# FanManager.net
KiCad netlist of a schematic drawn in EAGLE
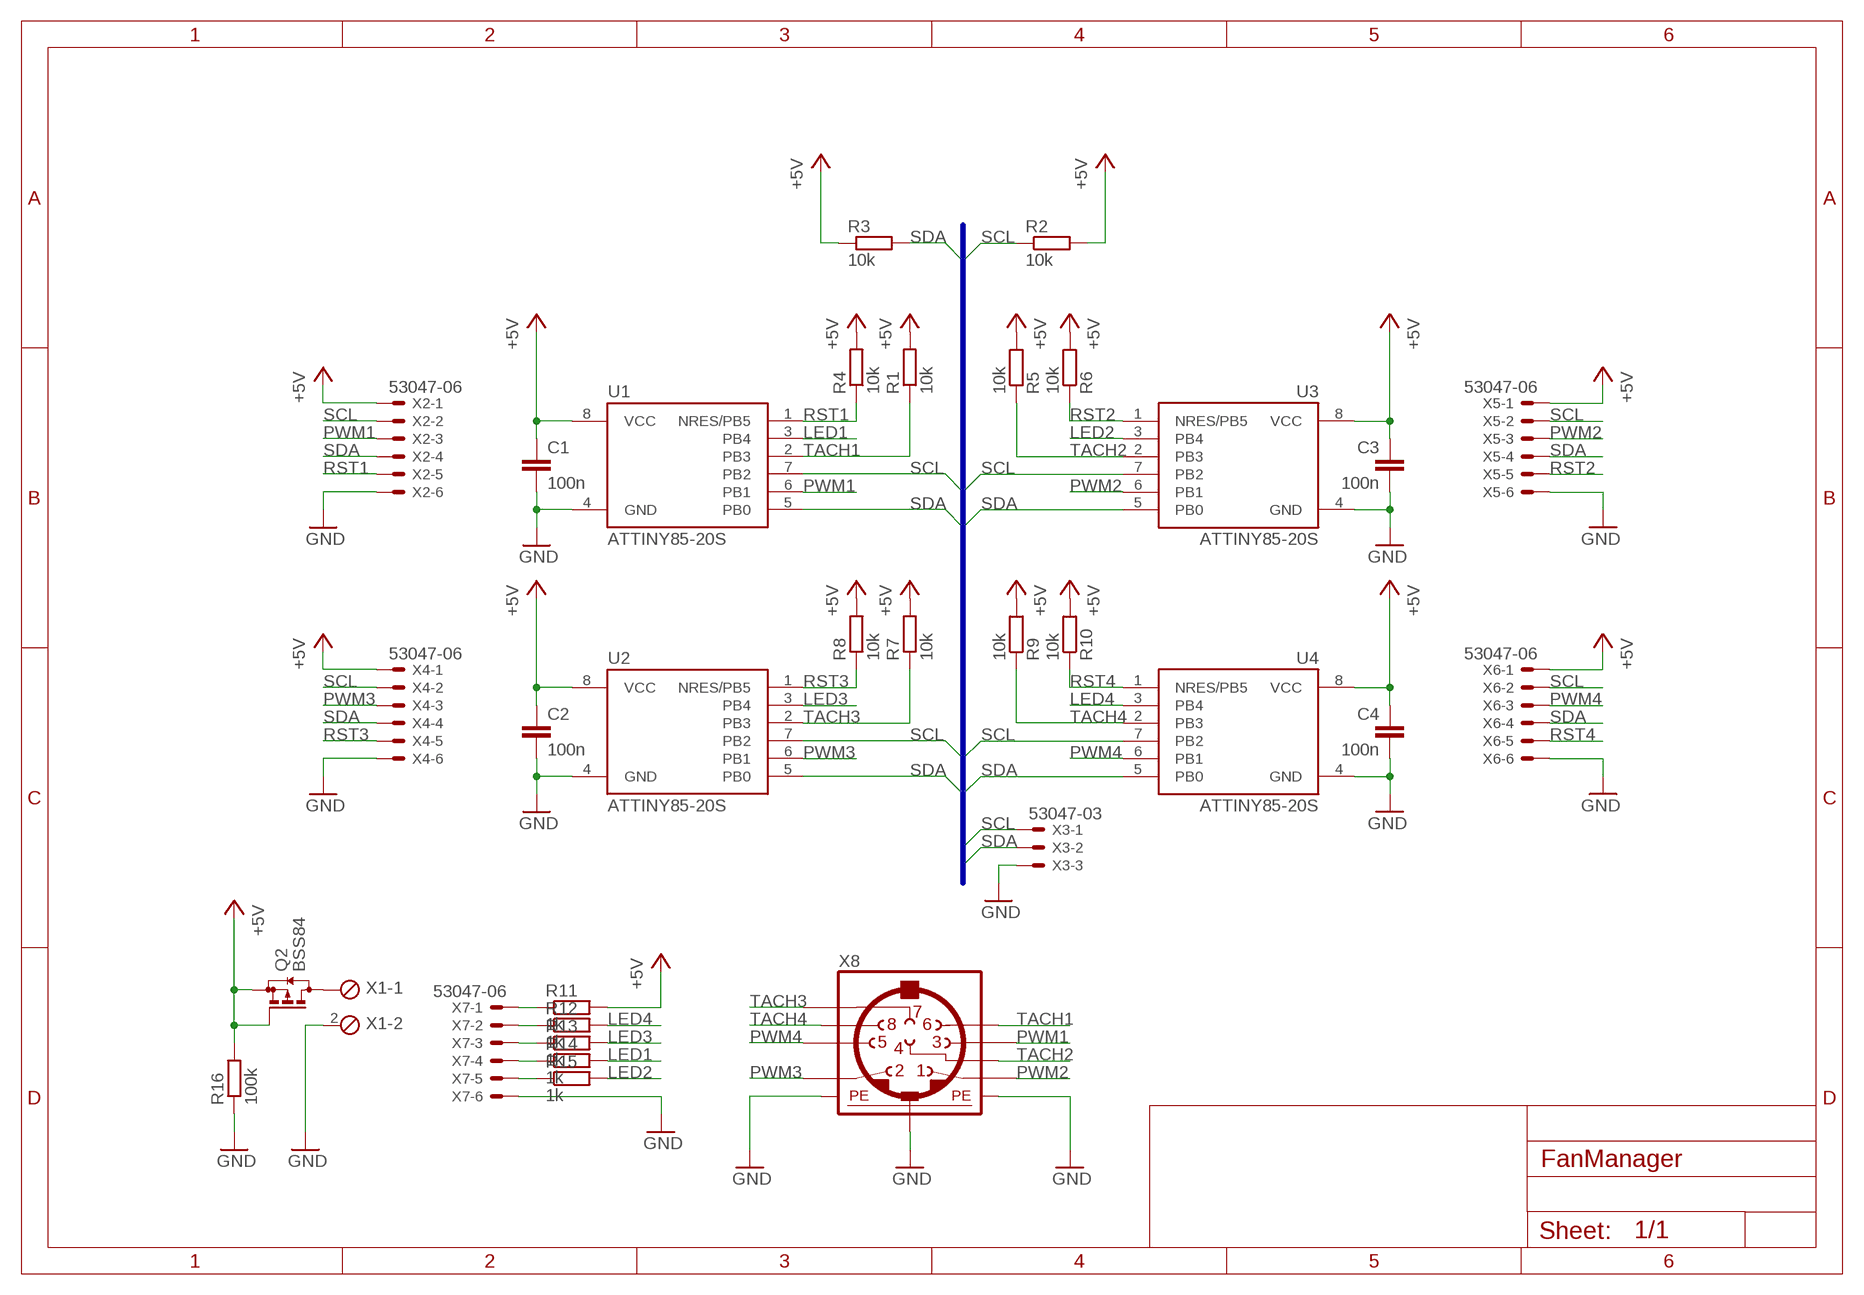
[diagram p0: schematic, sheet 1]

(export (version "E")
  (design (tool "Eeschema 10.0.6"))
  (components
    (comp (ref "C1")
      (value "100n")
      (footprint "eagle-import:C0805")
      (libsource (lib "eagle-import") (part "C-EUC0805"))
    )
    (comp (ref "C2")
      (value "100n")
      (footprint "eagle-import:C0805")
      (libsource (lib "eagle-import") (part "C-EUC0805"))
    )
    (comp (ref "C3")
      (value "100n")
      (footprint "eagle-import:C0805")
      (libsource (lib "eagle-import") (part "C-EUC0805"))
    )
    (comp (ref "C4")
      (value "100n")
      (footprint "eagle-import:C0805")
      (libsource (lib "eagle-import") (part "C-EUC0805"))
    )
    (comp (ref "Q2")
      (value "BSS84")
      (footprint "eagle-import:SOT23")
      (libsource (lib "eagle-import") (part "BSS84"))
    )
    (comp (ref "R1")
      (value "10k")
      (footprint "eagle-import:R0805")
      (libsource (lib "eagle-import") (part "R-EU_R0805"))
    )
    (comp (ref "R2")
      (value "10k")
      (footprint "eagle-import:R0805")
      (libsource (lib "eagle-import") (part "R-EU_R0805"))
    )
    (comp (ref "R3")
      (value "10k")
      (footprint "eagle-import:R0805")
      (libsource (lib "eagle-import") (part "R-EU_R0805"))
    )
    (comp (ref "R4")
      (value "10k")
      (footprint "eagle-import:R0805")
      (libsource (lib "eagle-import") (part "R-EU_R0805"))
    )
    (comp (ref "R5")
      (value "10k")
      (footprint "eagle-import:R0805")
      (libsource (lib "eagle-import") (part "R-EU_R0805"))
    )
    (comp (ref "R6")
      (value "10k")
      (footprint "eagle-import:R0805")
      (libsource (lib "eagle-import") (part "R-EU_R0805"))
    )
    (comp (ref "R7")
      (value "10k")
      (footprint "eagle-import:R0805")
      (libsource (lib "eagle-import") (part "R-EU_R0805"))
    )
    (comp (ref "R8")
      (value "10k")
      (footprint "eagle-import:R0805")
      (libsource (lib "eagle-import") (part "R-EU_R0805"))
    )
    (comp (ref "R9")
      (value "10k")
      (footprint "eagle-import:R0805")
      (libsource (lib "eagle-import") (part "R-EU_R0805"))
    )
    (comp (ref "R10")
      (value "10k")
      (footprint "eagle-import:R0805")
      (libsource (lib "eagle-import") (part "R-EU_R0805"))
    )
    (comp (ref "R11")
      (value "1k")
      (footprint "eagle-import:R0805")
      (libsource (lib "eagle-import") (part "R-EU_R0805"))
    )
    (comp (ref "R12")
      (value "1k")
      (footprint "eagle-import:R0805")
      (libsource (lib "eagle-import") (part "R-EU_R0805"))
    )
    (comp (ref "R13")
      (value "1k")
      (footprint "eagle-import:R0805")
      (libsource (lib "eagle-import") (part "R-EU_R0805"))
    )
    (comp (ref "R14")
      (value "1k")
      (footprint "eagle-import:R0805")
      (libsource (lib "eagle-import") (part "R-EU_R0805"))
    )
    (comp (ref "R15")
      (value "1k")
      (footprint "eagle-import:R0805")
      (libsource (lib "eagle-import") (part "R-EU_R0805"))
    )
    (comp (ref "R16")
      (value "100k")
      (footprint "eagle-import:R0805")
      (libsource (lib "eagle-import") (part "R-EU_R0805"))
    )
    (comp (ref "U1")
      (value "ATTINY85-20S")
      (footprint "eagle-import:SOIC8_EIAJ_208MIL")
      (libsource (lib "eagle-import") (part "ATTINY85S-20"))
    )
    (comp (ref "U2")
      (value "ATTINY85-20S")
      (footprint "eagle-import:SOIC8_EIAJ_208MIL")
      (libsource (lib "eagle-import") (part "ATTINY85S-20"))
    )
    (comp (ref "U3")
      (value "ATTINY85-20S")
      (footprint "eagle-import:SOIC8_EIAJ_208MIL")
      (libsource (lib "eagle-import") (part "ATTINY85S-20"))
    )
    (comp (ref "U4")
      (value "ATTINY85-20S")
      (footprint "eagle-import:SOIC8_EIAJ_208MIL")
      (libsource (lib "eagle-import") (part "ATTINY85S-20"))
    )
    (comp (ref "X1")
      (value "KLEMME_2XRAND_LANGPAD")
      (footprint "eagle-import:2POL254")
      (libsource (lib "eagle-import") (part "KLEMME_2XRAND_LANGPAD"))
    )
    (comp (ref "X2")
      (value "53047-06")
      (footprint "eagle-import:53047-06")
      (fields (field (name "MF") "MOLEX") (field (name "MPN") "53047-0610-C"))
      (libsource (lib "eagle-import") (part "53?-06047"))
    )
    (comp (ref "X3")
      (value "53047-03")
      (footprint "eagle-import:53047-03")
      (fields (field (name "MF") "MOLEX") (field (name "MPN") "530470310"))
      (libsource (lib "eagle-import") (part "53?-03047"))
    )
    (comp (ref "X4")
      (value "53047-06")
      (footprint "eagle-import:53047-06")
      (fields (field (name "MF") "MOLEX") (field (name "MPN") "53047-0610-C"))
      (libsource (lib "eagle-import") (part "53?-06047"))
    )
    (comp (ref "X5")
      (value "53047-06")
      (footprint "eagle-import:53047-06")
      (fields (field (name "MF") "MOLEX") (field (name "MPN") "53047-0610-C"))
      (libsource (lib "eagle-import") (part "53?-06047"))
    )
    (comp (ref "X6")
      (value "53047-06")
      (footprint "eagle-import:53047-06")
      (fields (field (name "MF") "MOLEX") (field (name "MPN") "53047-0610-C"))
      (libsource (lib "eagle-import") (part "53?-06047"))
    )
    (comp (ref "X7")
      (value "53047-06")
      (footprint "eagle-import:53047-06")
      (fields (field (name "MF") "MOLEX") (field (name "MPN") "53047-0610-C"))
      (libsource (lib "eagle-import") (part "53?-06047"))
    )
    (comp (ref "X8")
      (value "MINI_DIN_8")
      (footprint "eagle-import:M_DIN8")
      (libsource (lib "eagle-import") (part "MINI_DIN_8"))
    )
  )
  (nets
    (net (code "1") (name "+5V") (class "Default")
      (node (ref "C1") (pin "1") (pinfunction "1_1") (pintype "passive"))
      (node (ref "C2") (pin "1") (pinfunction "1_1") (pintype "passive"))
      (node (ref "C3") (pin "1") (pinfunction "1_1") (pintype "passive"))
      (node (ref "C4") (pin "1") (pinfunction "1_1") (pintype "passive"))
      (node (ref "Q2") (pin "1") (pinfunction "G_1") (pintype "passive"))
      (node (ref "Q2") (pin "2") (pinfunction "S_2") (pintype "passive"))
      (node (ref "R1") (pin "2") (pinfunction "2_2") (pintype "passive"))
      (node (ref "R10") (pin "2") (pinfunction "2_2") (pintype "passive"))
      (node (ref "R11") (pin "2") (pinfunction "2_2") (pintype "passive"))
      (node (ref "R16") (pin "2") (pinfunction "2_2") (pintype "passive"))
      (node (ref "R2") (pin "2") (pinfunction "2_2") (pintype "passive"))
      (node (ref "R3") (pin "1") (pinfunction "1_1") (pintype "passive"))
      (node (ref "R4") (pin "2") (pinfunction "2_2") (pintype "passive"))
      (node (ref "R5") (pin "2") (pinfunction "2_2") (pintype "passive"))
      (node (ref "R6") (pin "2") (pinfunction "2_2") (pintype "passive"))
      (node (ref "R7") (pin "2") (pinfunction "2_2") (pintype "passive"))
      (node (ref "R8") (pin "2") (pinfunction "2_2") (pintype "passive"))
      (node (ref "R9") (pin "2") (pinfunction "2_2") (pintype "passive"))
      (node (ref "U1") (pin "8") (pinfunction "VCC_8") (pintype "power_in"))
      (node (ref "U2") (pin "8") (pinfunction "VCC_8") (pintype "power_in"))
      (node (ref "U3") (pin "8") (pinfunction "VCC_8") (pintype "power_in"))
      (node (ref "U4") (pin "8") (pinfunction "VCC_8") (pintype "power_in"))
      (node (ref "X2") (pin "1") (pinfunction "S_1") (pintype "passive"))
      (node (ref "X4") (pin "1") (pinfunction "S_1") (pintype "passive"))
      (node (ref "X5") (pin "1") (pinfunction "S_1") (pintype "passive"))
      (node (ref "X6") (pin "1") (pinfunction "S_1") (pintype "passive"))
    )
    (net (code "2") (name "/LED1") (class "Default")
      (node (ref "R14") (pin "2") (pinfunction "2_2") (pintype "passive"))
      (node (ref "U1") (pin "3") (pinfunction "PB4_3") (pintype "bidirectional"))
    )
    (net (code "3") (name "/LED2") (class "Default")
      (node (ref "R15") (pin "2") (pinfunction "2_2") (pintype "passive"))
      (node (ref "U3") (pin "3") (pinfunction "PB4_3") (pintype "bidirectional"))
    )
    (net (code "4") (name "/LED3") (class "Default")
      (node (ref "R13") (pin "2") (pinfunction "2_2") (pintype "passive"))
      (node (ref "U2") (pin "3") (pinfunction "PB4_3") (pintype "bidirectional"))
    )
    (net (code "5") (name "/LED4") (class "Default")
      (node (ref "R12") (pin "2") (pinfunction "2_2") (pintype "passive"))
      (node (ref "U4") (pin "3") (pinfunction "PB4_3") (pintype "bidirectional"))
    )
    (net (code "6") (name "/PWM1") (class "Default")
      (node (ref "U1") (pin "6") (pinfunction "PB1_6") (pintype "bidirectional"))
      (node (ref "X2") (pin "3") (pinfunction "S_3") (pintype "passive"))
      (node (ref "X8") (pin "3") (pinfunction "3_3") (pintype "passive"))
    )
    (net (code "7") (name "/PWM2") (class "Default")
      (node (ref "U3") (pin "6") (pinfunction "PB1_6") (pintype "bidirectional"))
      (node (ref "X5") (pin "3") (pinfunction "S_3") (pintype "passive"))
      (node (ref "X8") (pin "1") (pinfunction "1_1") (pintype "passive"))
    )
    (net (code "8") (name "/PWM3") (class "Default")
      (node (ref "U2") (pin "6") (pinfunction "PB1_6") (pintype "bidirectional"))
      (node (ref "X4") (pin "3") (pinfunction "S_3") (pintype "passive"))
      (node (ref "X8") (pin "2") (pinfunction "2_2") (pintype "passive"))
    )
    (net (code "9") (name "/PWM4") (class "Default")
      (node (ref "U4") (pin "6") (pinfunction "PB1_6") (pintype "bidirectional"))
      (node (ref "X6") (pin "3") (pinfunction "S_3") (pintype "passive"))
      (node (ref "X8") (pin "5") (pinfunction "5_5") (pintype "passive"))
    )
    (net (code "10") (name "/RST1") (class "Default")
      (node (ref "R4") (pin "1") (pinfunction "1_1") (pintype "passive"))
      (node (ref "U1") (pin "1") (pinfunction "NRES/PB5_1") (pintype "bidirectional"))
      (node (ref "X2") (pin "5") (pinfunction "S_5") (pintype "passive"))
    )
    (net (code "11") (name "/RST2") (class "Default")
      (node (ref "R6") (pin "1") (pinfunction "1_1") (pintype "passive"))
      (node (ref "U3") (pin "1") (pinfunction "NRES/PB5_1") (pintype "bidirectional"))
      (node (ref "X5") (pin "5") (pinfunction "S_5") (pintype "passive"))
    )
    (net (code "12") (name "/RST3") (class "Default")
      (node (ref "R8") (pin "1") (pinfunction "1_1") (pintype "passive"))
      (node (ref "U2") (pin "1") (pinfunction "NRES/PB5_1") (pintype "bidirectional"))
      (node (ref "X4") (pin "5") (pinfunction "S_5") (pintype "passive"))
    )
    (net (code "13") (name "/RST4") (class "Default")
      (node (ref "R10") (pin "1") (pinfunction "1_1") (pintype "passive"))
      (node (ref "U4") (pin "1") (pinfunction "NRES/PB5_1") (pintype "bidirectional"))
      (node (ref "X6") (pin "5") (pinfunction "S_5") (pintype "passive"))
    )
    (net (code "14") (name "/SCL") (class "Default")
      (node (ref "R2") (pin "1") (pinfunction "1_1") (pintype "passive"))
      (node (ref "U1") (pin "7") (pinfunction "PB2_7") (pintype "bidirectional"))
      (node (ref "U2") (pin "7") (pinfunction "PB2_7") (pintype "bidirectional"))
      (node (ref "U3") (pin "7") (pinfunction "PB2_7") (pintype "bidirectional"))
      (node (ref "U4") (pin "7") (pinfunction "PB2_7") (pintype "bidirectional"))
      (node (ref "X2") (pin "2") (pinfunction "S_2") (pintype "passive"))
      (node (ref "X3") (pin "1") (pinfunction "S_1") (pintype "passive"))
      (node (ref "X4") (pin "2") (pinfunction "S_2") (pintype "passive"))
      (node (ref "X5") (pin "2") (pinfunction "S_2") (pintype "passive"))
      (node (ref "X6") (pin "2") (pinfunction "S_2") (pintype "passive"))
    )
    (net (code "15") (name "/SDA") (class "Default")
      (node (ref "R3") (pin "2") (pinfunction "2_2") (pintype "passive"))
      (node (ref "U1") (pin "5") (pinfunction "PB0_5") (pintype "bidirectional"))
      (node (ref "U2") (pin "5") (pinfunction "PB0_5") (pintype "bidirectional"))
      (node (ref "U3") (pin "5") (pinfunction "PB0_5") (pintype "bidirectional"))
      (node (ref "U4") (pin "5") (pinfunction "PB0_5") (pintype "bidirectional"))
      (node (ref "X2") (pin "4") (pinfunction "S_4") (pintype "passive"))
      (node (ref "X3") (pin "2") (pinfunction "S_2") (pintype "passive"))
      (node (ref "X4") (pin "4") (pinfunction "S_4") (pintype "passive"))
      (node (ref "X5") (pin "4") (pinfunction "S_4") (pintype "passive"))
      (node (ref "X6") (pin "4") (pinfunction "S_4") (pintype "passive"))
    )
    (net (code "16") (name "/TACH1") (class "Default")
      (node (ref "R1") (pin "1") (pinfunction "1_1") (pintype "passive"))
      (node (ref "U1") (pin "2") (pinfunction "PB3_2") (pintype "bidirectional"))
      (node (ref "X8") (pin "6") (pinfunction "6_6") (pintype "passive"))
    )
    (net (code "17") (name "/TACH2") (class "Default")
      (node (ref "R5") (pin "1") (pinfunction "1_1") (pintype "passive"))
      (node (ref "U3") (pin "2") (pinfunction "PB3_2") (pintype "bidirectional"))
      (node (ref "X8") (pin "4") (pinfunction "4_4") (pintype "passive"))
    )
    (net (code "18") (name "/TACH3") (class "Default")
      (node (ref "R7") (pin "1") (pinfunction "1_1") (pintype "passive"))
      (node (ref "U2") (pin "2") (pinfunction "PB3_2") (pintype "bidirectional"))
      (node (ref "X8") (pin "7") (pinfunction "7_7") (pintype "passive"))
    )
    (net (code "19") (name "/TACH4") (class "Default")
      (node (ref "R9") (pin "1") (pinfunction "1_1") (pintype "passive"))
      (node (ref "U4") (pin "2") (pinfunction "PB3_2") (pintype "bidirectional"))
      (node (ref "X8") (pin "8") (pinfunction "8_8") (pintype "passive"))
    )
    (net (code "20") (name "GND") (class "Default")
      (node (ref "C1") (pin "2") (pinfunction "2_2") (pintype "passive"))
      (node (ref "C2") (pin "2") (pinfunction "2_2") (pintype "passive"))
      (node (ref "C3") (pin "2") (pinfunction "2_2") (pintype "passive"))
      (node (ref "C4") (pin "2") (pinfunction "2_2") (pintype "passive"))
      (node (ref "R16") (pin "1") (pinfunction "1_1") (pintype "passive"))
      (node (ref "U1") (pin "4") (pinfunction "GND_4") (pintype "power_in"))
      (node (ref "U2") (pin "4") (pinfunction "GND_4") (pintype "power_in"))
      (node (ref "U3") (pin "4") (pinfunction "GND_4") (pintype "power_in"))
      (node (ref "U4") (pin "4") (pinfunction "GND_4") (pintype "power_in"))
      (node (ref "X1") (pin "2") (pinfunction "1_2") (pintype "passive"))
      (node (ref "X2") (pin "6") (pinfunction "S_6") (pintype "passive"))
      (node (ref "X3") (pin "3") (pinfunction "S_3") (pintype "passive"))
      (node (ref "X4") (pin "6") (pinfunction "S_6") (pintype "passive"))
      (node (ref "X5") (pin "6") (pinfunction "S_6") (pintype "passive"))
      (node (ref "X6") (pin "6") (pinfunction "S_6") (pintype "passive"))
      (node (ref "X7") (pin "6") (pinfunction "S_6") (pintype "passive"))
      (node (ref "X8") (pin "SH1") (pinfunction "PE1_SH1") (pintype "power_in"))
      (node (ref "X8") (pin "SH2") (pinfunction "PE2_SH2") (pintype "power_in"))
      (node (ref "X8") (pin "SH3") (pinfunction "PE3_SH3") (pintype "power_in"))
    )
    (net (code "21") (name "Net-(Q2-D)") (class "Default")
      (node (ref "Q2") (pin "3") (pinfunction "D_3") (pintype "passive"))
      (node (ref "X1") (pin "1") (pinfunction "1_1") (pintype "passive"))
    )
    (net (code "22") (name "Net-(X7A-S)") (class "Default")
      (node (ref "R11") (pin "1") (pinfunction "1_1") (pintype "passive"))
      (node (ref "X7") (pin "1") (pinfunction "S_1") (pintype "passive"))
    )
    (net (code "23") (name "Net-(X7B-S)") (class "Default")
      (node (ref "R12") (pin "1") (pinfunction "1_1") (pintype "passive"))
      (node (ref "X7") (pin "2") (pinfunction "S_2") (pintype "passive"))
    )
    (net (code "24") (name "Net-(X7C-S)") (class "Default")
      (node (ref "R13") (pin "1") (pinfunction "1_1") (pintype "passive"))
      (node (ref "X7") (pin "3") (pinfunction "S_3") (pintype "passive"))
    )
    (net (code "25") (name "Net-(X7D-S)") (class "Default")
      (node (ref "R14") (pin "1") (pinfunction "1_1") (pintype "passive"))
      (node (ref "X7") (pin "4") (pinfunction "S_4") (pintype "passive"))
    )
    (net (code "26") (name "Net-(X7E-S)") (class "Default")
      (node (ref "R15") (pin "1") (pinfunction "1_1") (pintype "passive"))
      (node (ref "X7") (pin "5") (pinfunction "S_5") (pintype "passive"))
    )
  )
)
